# SCH_relayboard.net
KiCad netlist of a schematic drawn in EasyEDA
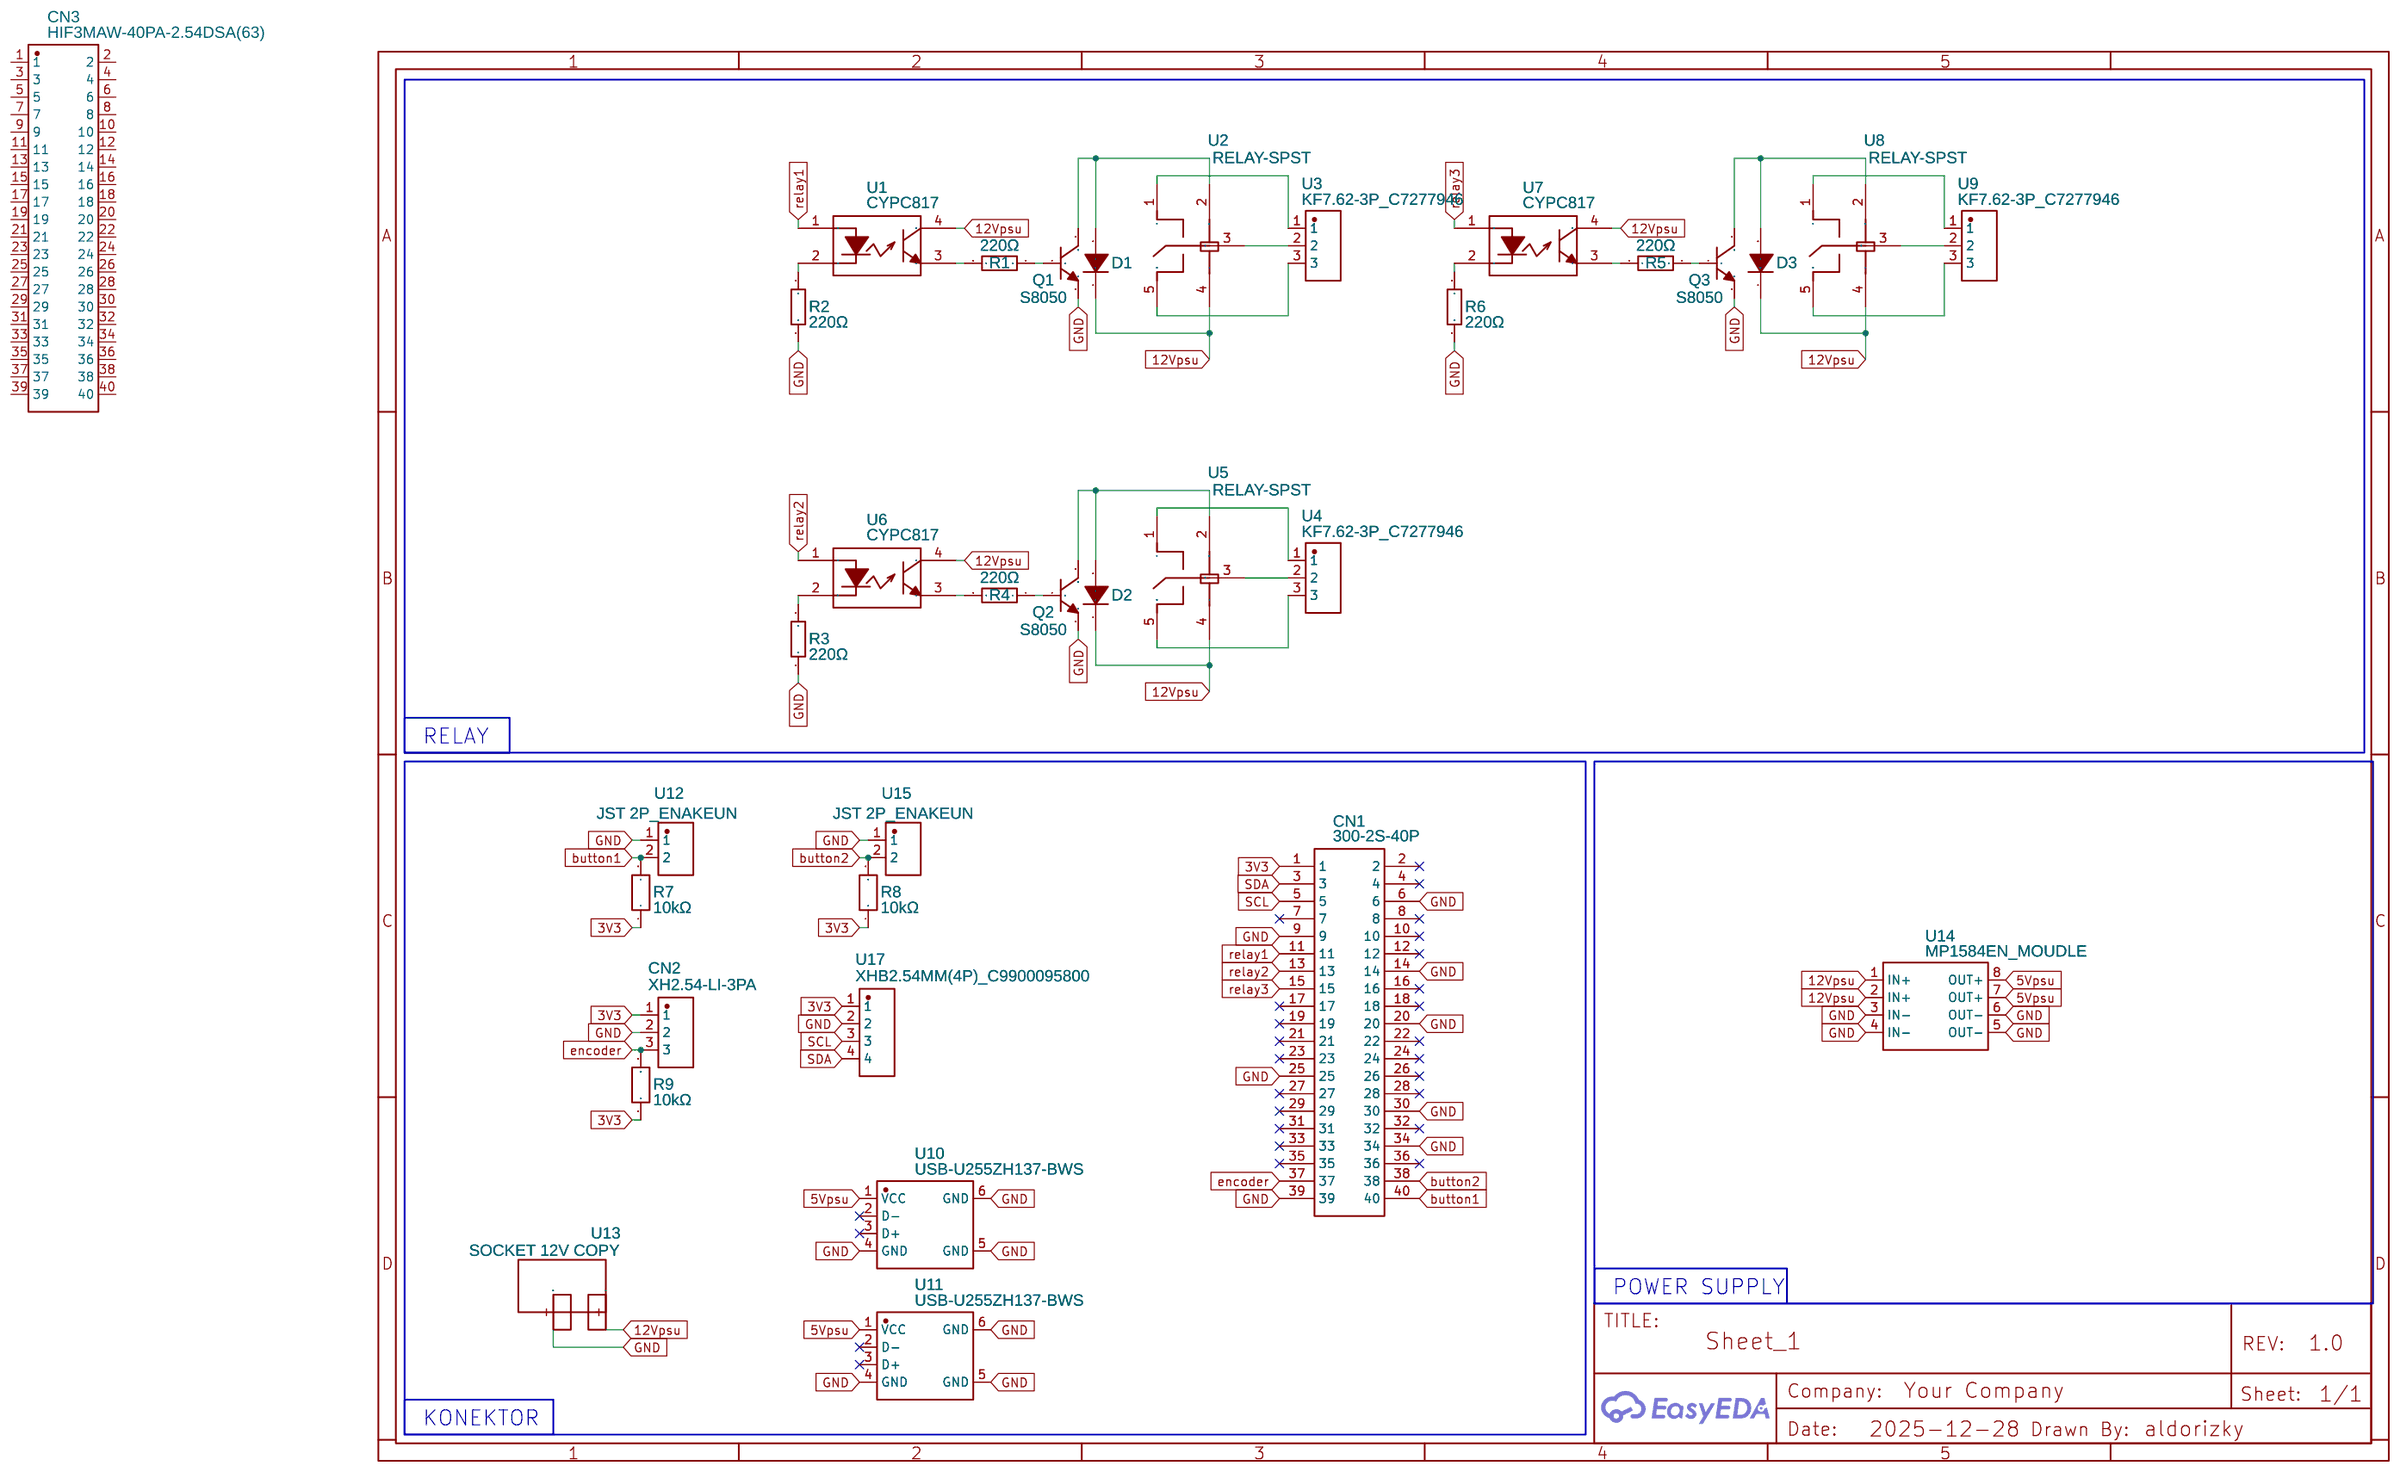
[diagram p0: schematic sheet]

(export (version "E")
  (design (tool "Eeschema 10.0.6"))
  (components
    (comp (ref "CN1")
      (value "300-2S-40P")
      (fields (field (name "Manufacturer Part") "B-3002S40P-0110") (field (name "Manufacturer") "Ckmtw(灿科盟)"))
      (libsource (lib "") (part "300-2S-40P"))
    )
    (comp (ref "CN2") (value "XH2.54-LI-3PA") (libsource (lib "") (part "XH2.54-LI-3PA")))
    (comp (ref "CN3")
      (value "HIF3MAW-40PA-2.54DSA(63)")
      (fields (field (name "Manufacturer") "HRS(广濑)"))
      (libsource (lib "") (part "HIF3MAW-40PA-2.54DSA(63)"))
    )
    (comp (ref "D1")
      (value "1N4148WL")
      (fields (field (name "Manufacturer") "晶导微电子"))
      (libsource (lib "") (part "1N4148WL"))
    )
    (comp (ref "D2")
      (value "1N4148WL")
      (fields (field (name "Manufacturer") "晶导微电子"))
      (libsource (lib "") (part "1N4148WL"))
    )
    (comp (ref "D3")
      (value "1N4148WL")
      (fields (field (name "Manufacturer") "晶导微电子"))
      (libsource (lib "") (part "1N4148WL"))
    )
    (comp (ref "Q1")
      (value "S8050")
      (fields (field (name "Manufacturer") "JUXING(钜兴)"))
      (libsource (lib "") (part "S8050_C3011093"))
    )
    (comp (ref "Q2")
      (value "S8050")
      (fields (field (name "Manufacturer") "JUXING(钜兴)"))
      (libsource (lib "") (part "S8050_C3011093"))
    )
    (comp (ref "Q3")
      (value "S8050")
      (fields (field (name "Manufacturer") "JUXING(钜兴)"))
      (libsource (lib "") (part "S8050_C3011093"))
    )
    (comp (ref "R1")
      (value "220Ω")
      (fields (field (name "Manufacturer Part") "AC0603JR-07220RL") (field (name "Manufacturer") "YAGEO(国巨)"))
      (libsource (lib "") (part "AC0603JR-07220RL_1"))
    )
    (comp (ref "R2")
      (value "220Ω")
      (fields (field (name "Manufacturer Part") "AC0603JR-07220RL") (field (name "Manufacturer") "YAGEO(国巨)"))
      (libsource (lib "") (part "AC0603JR-07220RL"))
    )
    (comp (ref "R3")
      (value "220Ω")
      (fields (field (name "Manufacturer Part") "AC0603JR-07220RL") (field (name "Manufacturer") "YAGEO(国巨)"))
      (libsource (lib "") (part "AC0603JR-07220RL"))
    )
    (comp (ref "R4")
      (value "220Ω")
      (fields (field (name "Manufacturer Part") "AC0603JR-07220RL") (field (name "Manufacturer") "YAGEO(国巨)"))
      (libsource (lib "") (part "AC0603JR-07220RL_1"))
    )
    (comp (ref "R5")
      (value "220Ω")
      (fields (field (name "Manufacturer Part") "AC0603JR-07220RL") (field (name "Manufacturer") "YAGEO(国巨)"))
      (libsource (lib "") (part "AC0603JR-07220RL_1"))
    )
    (comp (ref "R6")
      (value "220Ω")
      (fields (field (name "Manufacturer Part") "AC0603JR-07220RL") (field (name "Manufacturer") "YAGEO(国巨)"))
      (libsource (lib "") (part "AC0603JR-07220RL"))
    )
    (comp (ref "R7")
      (value "10kΩ")
      (fields (field (name "Manufacturer Part") "RC0603FR-1010KL") (field (name "Manufacturer") "YAGEO(国巨)"))
      (libsource (lib "") (part "RC0603FR-1010KL"))
    )
    (comp (ref "R8")
      (value "10kΩ")
      (fields (field (name "Manufacturer Part") "RC0603FR-1010KL") (field (name "Manufacturer") "YAGEO(国巨)"))
      (libsource (lib "") (part "RC0603FR-1010KL"))
    )
    (comp (ref "R9")
      (value "10kΩ")
      (fields (field (name "Manufacturer Part") "RC0603FR-1010KL") (field (name "Manufacturer") "YAGEO(国巨)"))
      (libsource (lib "") (part "RC0603FR-1010KL"))
    )
    (comp (ref "U1")
      (value "CYPC817")
      (fields (field (name "Manufacturer Part") "CYPC817B") (field (name "Manufacturer") "OCIC(卓睿科)"))
      (libsource (lib "") (part "CYPC817"))
    )
    (comp (ref "U2")
      (value "RELAY-SPST")
      (fields (field (name "Manufacturer Part") "Relay-SPST"))
      (libsource (lib "") (part "RELAY-SPST"))
    )
    (comp (ref "U3")
      (value "KF7.62-3P_C7277946")
      (fields (field (name "Manufacturer Part") "KF7.62-3P") (field (name "Manufacturer") "KEFA(科发)"))
      (libsource (lib "") (part "KF7.62-3P_C7277946"))
    )
    (comp (ref "U4")
      (value "KF7.62-3P_C7277946")
      (fields (field (name "Manufacturer Part") "KF7.62-3P") (field (name "Manufacturer") "KEFA(科发)"))
      (libsource (lib "") (part "KF7.62-3P_C7277946"))
    )
    (comp (ref "U5")
      (value "RELAY-SPST")
      (fields (field (name "Manufacturer Part") "Relay-SPST"))
      (libsource (lib "") (part "RELAY-SPST"))
    )
    (comp (ref "U6")
      (value "CYPC817")
      (fields (field (name "Manufacturer Part") "CYPC817B") (field (name "Manufacturer") "OCIC(卓睿科)"))
      (libsource (lib "") (part "CYPC817"))
    )
    (comp (ref "U7")
      (value "CYPC817")
      (fields (field (name "Manufacturer Part") "CYPC817B") (field (name "Manufacturer") "OCIC(卓睿科)"))
      (libsource (lib "") (part "CYPC817"))
    )
    (comp (ref "U8")
      (value "RELAY-SPST")
      (fields (field (name "Manufacturer Part") "Relay-SPST"))
      (libsource (lib "") (part "RELAY-SPST"))
    )
    (comp (ref "U9")
      (value "KF7.62-3P_C7277946")
      (fields (field (name "Manufacturer Part") "KF7.62-3P") (field (name "Manufacturer") "KEFA(科发)"))
      (libsource (lib "") (part "KF7.62-3P_C7277946"))
    )
    (comp (ref "U10")
      (value "USB-U255ZH137-BWS")
      (fields (field (name "Manufacturer") "HANBO(汉博)"))
      (libsource (lib "") (part "USB-U255ZH137-BWS"))
    )
    (comp (ref "U11")
      (value "USB-U255ZH137-BWS")
      (fields (field (name "Manufacturer") "HANBO(汉博)"))
      (libsource (lib "") (part "USB-U255ZH137-BWS"))
    )
    (comp (ref "U12")
      (value "JST 2P_ENAKEUN")
      (fields (field (name "Manufacturer Part") "XH-2P-2.54"))
      (libsource (lib "") (part "JST 2P_ENAKEUN"))
    )
    (comp (ref "U13") (value "SOCKET 12V COPY") (libsource (lib "") (part "SOCKET 12V COPY")))
    (comp (ref "U14")
      (value "MP1584EN_MOUDLE")
      (fields (field (name "Manufacturer Part") "MP1584EN_moudle"))
      (libsource (lib "") (part "MP1584EN_MOUDLE"))
    )
    (comp (ref "U15")
      (value "JST 2P_ENAKEUN")
      (fields (field (name "Manufacturer Part") "XH-2P-2.54"))
      (libsource (lib "") (part "JST 2P_ENAKEUN"))
    )
    (comp (ref "U17")
      (value "XHB2.54MM(4P)_C9900095800")
      (fields (field (name "Manufacturer Part") "XHB2.54mm(4P)"))
      (libsource (lib "") (part "XHB2.54MM(4P)_C9900095800"))
    )
  )
  (nets
    (net (code "1") (name "3V3") (class "Default")
      (node (ref "CN1") (pin "1") (pinfunction "1_1") (pintype "unspecified"))
      (node (ref "CN2") (pin "1") (pinfunction "1_1") (pintype "unspecified"))
      (node (ref "R7") (pin "1") (pinfunction "1_1") (pintype "unspecified"))
      (node (ref "R8") (pin "1") (pinfunction "1_1") (pintype "unspecified"))
      (node (ref "R9") (pin "1") (pinfunction "1_1") (pintype "unspecified"))
      (node (ref "U17") (pin "1") (pinfunction "1_1") (pintype "unspecified"))
    )
    (net (code "2") (name "5Vpsu") (class "Default")
      (node (ref "U10") (pin "1") (pinfunction "VCC_1") (pintype "unspecified"))
      (node (ref "U11") (pin "1") (pinfunction "VCC_1") (pintype "unspecified"))
      (node (ref "U14") (pin "7") (pinfunction "OUT+_7") (pintype "unspecified"))
      (node (ref "U14") (pin "8") (pinfunction "OUT+_8") (pintype "unspecified"))
    )
    (net (code "3") (name "12Vpsu") (class "Default")
      (node (ref "D1") (pin "1") (pinfunction "C_1") (pintype "unspecified"))
      (node (ref "D2") (pin "1") (pinfunction "C_1") (pintype "unspecified"))
      (node (ref "D3") (pin "1") (pinfunction "C_1") (pintype "unspecified"))
      (node (ref "U1") (pin "4") (pinfunction "COL_4") (pintype "unspecified"))
      (node (ref "U13") (pin "+") (pinfunction "1_+") (pintype "unspecified"))
      (node (ref "U14") (pin "1") (pinfunction "IN+_1") (pintype "unspecified"))
      (node (ref "U14") (pin "2") (pinfunction "IN+_2") (pintype "unspecified"))
      (node (ref "U2") (pin "4") (pinfunction "4_4") (pintype "unspecified"))
      (node (ref "U5") (pin "4") (pinfunction "4_4") (pintype "unspecified"))
      (node (ref "U6") (pin "4") (pinfunction "COL_4") (pintype "unspecified"))
      (node (ref "U7") (pin "4") (pinfunction "COL_4") (pintype "unspecified"))
      (node (ref "U8") (pin "4") (pinfunction "4_4") (pintype "unspecified"))
    )
    (net (code "4") (name "GND") (class "Default")
      (node (ref "CN1") (pin "14") (pinfunction "14_14") (pintype "unspecified"))
      (node (ref "CN1") (pin "20") (pinfunction "20_20") (pintype "unspecified"))
      (node (ref "CN1") (pin "25") (pinfunction "25_25") (pintype "unspecified"))
      (node (ref "CN1") (pin "30") (pinfunction "30_30") (pintype "unspecified"))
      (node (ref "CN1") (pin "34") (pinfunction "34_34") (pintype "unspecified"))
      (node (ref "CN1") (pin "39") (pinfunction "39_39") (pintype "unspecified"))
      (node (ref "CN1") (pin "6") (pinfunction "6_6") (pintype "unspecified"))
      (node (ref "CN1") (pin "9") (pinfunction "9_9") (pintype "unspecified"))
      (node (ref "CN2") (pin "2") (pinfunction "2_2") (pintype "unspecified"))
      (node (ref "Q1") (pin "2") (pinfunction "E_2") (pintype "unspecified"))
      (node (ref "Q2") (pin "2") (pinfunction "E_2") (pintype "unspecified"))
      (node (ref "Q3") (pin "2") (pinfunction "E_2") (pintype "unspecified"))
      (node (ref "R2") (pin "1") (pinfunction "1_1") (pintype "unspecified"))
      (node (ref "R3") (pin "1") (pinfunction "1_1") (pintype "unspecified"))
      (node (ref "R6") (pin "1") (pinfunction "1_1") (pintype "unspecified"))
      (node (ref "U10") (pin "4") (pinfunction "GND_4") (pintype "unspecified"))
      (node (ref "U10") (pin "5") (pinfunction "GND_5") (pintype "unspecified"))
      (node (ref "U10") (pin "6") (pinfunction "GND_6") (pintype "unspecified"))
      (node (ref "U11") (pin "4") (pinfunction "GND_4") (pintype "unspecified"))
      (node (ref "U11") (pin "5") (pinfunction "GND_5") (pintype "unspecified"))
      (node (ref "U11") (pin "6") (pinfunction "GND_6") (pintype "unspecified"))
      (node (ref "U12") (pin "1") (pinfunction "1_1") (pintype "unspecified"))
      (node (ref "U13") (pin "-") (pinfunction "2_-") (pintype "unspecified"))
      (node (ref "U14") (pin "3") (pinfunction "IN-_3") (pintype "unspecified"))
      (node (ref "U14") (pin "4") (pinfunction "IN-_4") (pintype "unspecified"))
      (node (ref "U14") (pin "5") (pinfunction "OUT-_5") (pintype "unspecified"))
      (node (ref "U14") (pin "6") (pinfunction "OUT-_6") (pintype "unspecified"))
      (node (ref "U15") (pin "1") (pinfunction "1_1") (pintype "unspecified"))
      (node (ref "U17") (pin "2") (pinfunction "2_2") (pintype "unspecified"))
    )
    (net (code "5") (name "Net-(D1-A)") (class "Default")
      (node (ref "D1") (pin "2") (pinfunction "A_2") (pintype "unspecified"))
      (node (ref "Q1") (pin "3") (pinfunction "C_3") (pintype "unspecified"))
      (node (ref "U2") (pin "2") (pinfunction "2_2") (pintype "unspecified"))
    )
    (net (code "6") (name "Net-(D2-A)") (class "Default")
      (node (ref "D2") (pin "2") (pinfunction "A_2") (pintype "unspecified"))
      (node (ref "Q2") (pin "3") (pinfunction "C_3") (pintype "unspecified"))
      (node (ref "U5") (pin "2") (pinfunction "2_2") (pintype "unspecified"))
    )
    (net (code "7") (name "Net-(D3-A)") (class "Default")
      (node (ref "D3") (pin "2") (pinfunction "A_2") (pintype "unspecified"))
      (node (ref "Q3") (pin "3") (pinfunction "C_3") (pintype "unspecified"))
      (node (ref "U8") (pin "2") (pinfunction "2_2") (pintype "unspecified"))
    )
    (net (code "8") (name "Net-(Q1-B)") (class "Default")
      (node (ref "Q1") (pin "1") (pinfunction "B_1") (pintype "unspecified"))
      (node (ref "R1") (pin "1") (pinfunction "1_1") (pintype "unspecified"))
    )
    (net (code "9") (name "Net-(Q2-B)") (class "Default")
      (node (ref "Q2") (pin "1") (pinfunction "B_1") (pintype "unspecified"))
      (node (ref "R4") (pin "1") (pinfunction "1_1") (pintype "unspecified"))
    )
    (net (code "10") (name "Net-(Q3-B)") (class "Default")
      (node (ref "Q3") (pin "1") (pinfunction "B_1") (pintype "unspecified"))
      (node (ref "R5") (pin "1") (pinfunction "1_1") (pintype "unspecified"))
    )
    (net (code "11") (name "Net-(U1-CAT)") (class "Default")
      (node (ref "R2") (pin "2") (pinfunction "2_2") (pintype "unspecified"))
      (node (ref "U1") (pin "2") (pinfunction "CAT_2") (pintype "unspecified"))
    )
    (net (code "12") (name "Net-(U1-EM)") (class "Default")
      (node (ref "R1") (pin "2") (pinfunction "2_2") (pintype "unspecified"))
      (node (ref "U1") (pin "3") (pinfunction "EM_3") (pintype "unspecified"))
    )
    (net (code "13") (name "Net-(U2-Pad1)") (class "Default")
      (node (ref "U2") (pin "1") (pinfunction "1_1") (pintype "unspecified"))
      (node (ref "U3") (pin "1") (pinfunction "1_1") (pintype "unspecified"))
    )
    (net (code "14") (name "Net-(U2-Pad3)") (class "Default")
      (node (ref "U2") (pin "3") (pinfunction "3_3") (pintype "unspecified"))
      (node (ref "U3") (pin "2") (pinfunction "2_2") (pintype "unspecified"))
    )
    (net (code "15") (name "Net-(U2-Pad5)") (class "Default")
      (node (ref "U2") (pin "5") (pinfunction "5_5") (pintype "unspecified"))
      (node (ref "U3") (pin "3") (pinfunction "3_3") (pintype "unspecified"))
    )
    (net (code "16") (name "Net-(U4-Pad1)") (class "Default")
      (node (ref "U4") (pin "1") (pinfunction "1_1") (pintype "unspecified"))
      (node (ref "U5") (pin "1") (pinfunction "1_1") (pintype "unspecified"))
    )
    (net (code "17") (name "Net-(U4-Pad2)") (class "Default")
      (node (ref "U4") (pin "2") (pinfunction "2_2") (pintype "unspecified"))
      (node (ref "U5") (pin "3") (pinfunction "3_3") (pintype "unspecified"))
    )
    (net (code "18") (name "Net-(U4-Pad3)") (class "Default")
      (node (ref "U4") (pin "3") (pinfunction "3_3") (pintype "unspecified"))
      (node (ref "U5") (pin "5") (pinfunction "5_5") (pintype "unspecified"))
    )
    (net (code "19") (name "Net-(U6-CAT)") (class "Default")
      (node (ref "R3") (pin "2") (pinfunction "2_2") (pintype "unspecified"))
      (node (ref "U6") (pin "2") (pinfunction "CAT_2") (pintype "unspecified"))
    )
    (net (code "20") (name "Net-(U6-EM)") (class "Default")
      (node (ref "R4") (pin "2") (pinfunction "2_2") (pintype "unspecified"))
      (node (ref "U6") (pin "3") (pinfunction "EM_3") (pintype "unspecified"))
    )
    (net (code "21") (name "Net-(U7-CAT)") (class "Default")
      (node (ref "R6") (pin "2") (pinfunction "2_2") (pintype "unspecified"))
      (node (ref "U7") (pin "2") (pinfunction "CAT_2") (pintype "unspecified"))
    )
    (net (code "22") (name "Net-(U7-EM)") (class "Default")
      (node (ref "R5") (pin "2") (pinfunction "2_2") (pintype "unspecified"))
      (node (ref "U7") (pin "3") (pinfunction "EM_3") (pintype "unspecified"))
    )
    (net (code "23") (name "Net-(U8-Pad1)") (class "Default")
      (node (ref "U8") (pin "1") (pinfunction "1_1") (pintype "unspecified"))
      (node (ref "U9") (pin "1") (pinfunction "1_1") (pintype "unspecified"))
    )
    (net (code "24") (name "Net-(U8-Pad3)") (class "Default")
      (node (ref "U8") (pin "3") (pinfunction "3_3") (pintype "unspecified"))
      (node (ref "U9") (pin "2") (pinfunction "2_2") (pintype "unspecified"))
    )
    (net (code "25") (name "Net-(U8-Pad5)") (class "Default")
      (node (ref "U8") (pin "5") (pinfunction "5_5") (pintype "unspecified"))
      (node (ref "U9") (pin "3") (pinfunction "3_3") (pintype "unspecified"))
    )
    (net (code "26") (name "SCL") (class "Default")
      (node (ref "CN1") (pin "5") (pinfunction "5_5") (pintype "unspecified"))
      (node (ref "U17") (pin "3") (pinfunction "3_3") (pintype "unspecified"))
    )
    (net (code "27") (name "SDA") (class "Default")
      (node (ref "CN1") (pin "3") (pinfunction "3_3") (pintype "unspecified"))
      (node (ref "U17") (pin "4") (pinfunction "4_4") (pintype "unspecified"))
    )
    (net (code "28") (name "button1") (class "Default")
      (node (ref "CN1") (pin "40") (pinfunction "40_40") (pintype "unspecified"))
      (node (ref "R7") (pin "2") (pinfunction "2_2") (pintype "unspecified"))
      (node (ref "U12") (pin "2") (pinfunction "2_2") (pintype "unspecified"))
    )
    (net (code "29") (name "button2") (class "Default")
      (node (ref "CN1") (pin "38") (pinfunction "38_38") (pintype "unspecified"))
      (node (ref "R8") (pin "2") (pinfunction "2_2") (pintype "unspecified"))
      (node (ref "U15") (pin "2") (pinfunction "2_2") (pintype "unspecified"))
    )
    (net (code "30") (name "encoder") (class "Default")
      (node (ref "CN1") (pin "37") (pinfunction "37_37") (pintype "unspecified"))
      (node (ref "CN2") (pin "3") (pinfunction "3_3") (pintype "unspecified"))
      (node (ref "R9") (pin "2") (pinfunction "2_2") (pintype "unspecified"))
    )
    (net (code "31") (name "relay1") (class "Default")
      (node (ref "CN1") (pin "11") (pinfunction "11_11") (pintype "unspecified"))
      (node (ref "U1") (pin "1") (pinfunction "AN_1") (pintype "unspecified"))
    )
    (net (code "32") (name "relay2") (class "Default")
      (node (ref "CN1") (pin "13") (pinfunction "13_13") (pintype "unspecified"))
      (node (ref "U6") (pin "1") (pinfunction "AN_1") (pintype "unspecified"))
    )
    (net (code "33") (name "relay3") (class "Default")
      (node (ref "CN1") (pin "15") (pinfunction "15_15") (pintype "unspecified"))
      (node (ref "U7") (pin "1") (pinfunction "AN_1") (pintype "unspecified"))
    )
    (net (code "34") (name "unconnected-(CN1-Pad2)") (class "Default")
      (node (ref "CN1") (pin "2") (pinfunction "2_2") (pintype "unspecified+no_connect"))
    )
    (net (code "35") (name "unconnected-(CN1-Pad4)") (class "Default")
      (node (ref "CN1") (pin "4") (pinfunction "4_4") (pintype "unspecified+no_connect"))
    )
    (net (code "36") (name "unconnected-(CN1-Pad7)") (class "Default")
      (node (ref "CN1") (pin "7") (pinfunction "7_7") (pintype "unspecified+no_connect"))
    )
    (net (code "37") (name "unconnected-(CN1-Pad8)") (class "Default")
      (node (ref "CN1") (pin "8") (pinfunction "8_8") (pintype "unspecified+no_connect"))
    )
    (net (code "38") (name "unconnected-(CN1-Pad10)") (class "Default")
      (node (ref "CN1") (pin "10") (pinfunction "10_10") (pintype "unspecified+no_connect"))
    )
    (net (code "39") (name "unconnected-(CN1-Pad12)") (class "Default")
      (node (ref "CN1") (pin "12") (pinfunction "12_12") (pintype "unspecified+no_connect"))
    )
    (net (code "40") (name "unconnected-(CN1-Pad16)") (class "Default")
      (node (ref "CN1") (pin "16") (pinfunction "16_16") (pintype "unspecified+no_connect"))
    )
    (net (code "41") (name "unconnected-(CN1-Pad17)") (class "Default")
      (node (ref "CN1") (pin "17") (pinfunction "17_17") (pintype "unspecified+no_connect"))
    )
    (net (code "42") (name "unconnected-(CN1-Pad18)") (class "Default")
      (node (ref "CN1") (pin "18") (pinfunction "18_18") (pintype "unspecified+no_connect"))
    )
    (net (code "43") (name "unconnected-(CN1-Pad19)") (class "Default")
      (node (ref "CN1") (pin "19") (pinfunction "19_19") (pintype "unspecified+no_connect"))
    )
    (net (code "44") (name "unconnected-(CN1-Pad21)") (class "Default")
      (node (ref "CN1") (pin "21") (pinfunction "21_21") (pintype "unspecified+no_connect"))
    )
    (net (code "45") (name "unconnected-(CN1-Pad22)") (class "Default")
      (node (ref "CN1") (pin "22") (pinfunction "22_22") (pintype "unspecified+no_connect"))
    )
    (net (code "46") (name "unconnected-(CN1-Pad23)") (class "Default")
      (node (ref "CN1") (pin "23") (pinfunction "23_23") (pintype "unspecified+no_connect"))
    )
    (net (code "47") (name "unconnected-(CN1-Pad24)") (class "Default")
      (node (ref "CN1") (pin "24") (pinfunction "24_24") (pintype "unspecified+no_connect"))
    )
    (net (code "48") (name "unconnected-(CN1-Pad26)") (class "Default")
      (node (ref "CN1") (pin "26") (pinfunction "26_26") (pintype "unspecified+no_connect"))
    )
    (net (code "49") (name "unconnected-(CN1-Pad27)") (class "Default")
      (node (ref "CN1") (pin "27") (pinfunction "27_27") (pintype "unspecified+no_connect"))
    )
    (net (code "50") (name "unconnected-(CN1-Pad28)") (class "Default")
      (node (ref "CN1") (pin "28") (pinfunction "28_28") (pintype "unspecified+no_connect"))
    )
    (net (code "51") (name "unconnected-(CN1-Pad29)") (class "Default")
      (node (ref "CN1") (pin "29") (pinfunction "29_29") (pintype "unspecified+no_connect"))
    )
    (net (code "52") (name "unconnected-(CN1-Pad31)") (class "Default")
      (node (ref "CN1") (pin "31") (pinfunction "31_31") (pintype "unspecified+no_connect"))
    )
    (net (code "53") (name "unconnected-(CN1-Pad32)") (class "Default")
      (node (ref "CN1") (pin "32") (pinfunction "32_32") (pintype "unspecified+no_connect"))
    )
    (net (code "54") (name "unconnected-(CN1-Pad33)") (class "Default")
      (node (ref "CN1") (pin "33") (pinfunction "33_33") (pintype "unspecified+no_connect"))
    )
    (net (code "55") (name "unconnected-(CN1-Pad35)") (class "Default")
      (node (ref "CN1") (pin "35") (pinfunction "35_35") (pintype "unspecified+no_connect"))
    )
    (net (code "56") (name "unconnected-(CN1-Pad36)") (class "Default")
      (node (ref "CN1") (pin "36") (pinfunction "36_36") (pintype "unspecified+no_connect"))
    )
    (net (code "57") (name "unconnected-(CN3-Pad1)") (class "Default")
      (node (ref "CN3") (pin "1") (pinfunction "1_1") (pintype "unspecified"))
    )
    (net (code "58") (name "unconnected-(CN3-Pad2)") (class "Default")
      (node (ref "CN3") (pin "2") (pinfunction "2_2") (pintype "unspecified"))
    )
    (net (code "59") (name "unconnected-(CN3-Pad3)") (class "Default")
      (node (ref "CN3") (pin "3") (pinfunction "3_3") (pintype "unspecified"))
    )
    (net (code "60") (name "unconnected-(CN3-Pad4)") (class "Default")
      (node (ref "CN3") (pin "4") (pinfunction "4_4") (pintype "unspecified"))
    )
    (net (code "61") (name "unconnected-(CN3-Pad5)") (class "Default")
      (node (ref "CN3") (pin "5") (pinfunction "5_5") (pintype "unspecified"))
    )
    (net (code "62") (name "unconnected-(CN3-Pad6)") (class "Default")
      (node (ref "CN3") (pin "6") (pinfunction "6_6") (pintype "unspecified"))
    )
    (net (code "63") (name "unconnected-(CN3-Pad7)") (class "Default")
      (node (ref "CN3") (pin "7") (pinfunction "7_7") (pintype "unspecified"))
    )
    (net (code "64") (name "unconnected-(CN3-Pad8)") (class "Default")
      (node (ref "CN3") (pin "8") (pinfunction "8_8") (pintype "unspecified"))
    )
    (net (code "65") (name "unconnected-(CN3-Pad9)") (class "Default")
      (node (ref "CN3") (pin "9") (pinfunction "9_9") (pintype "unspecified"))
    )
    (net (code "66") (name "unconnected-(CN3-Pad10)") (class "Default")
      (node (ref "CN3") (pin "10") (pinfunction "10_10") (pintype "unspecified"))
    )
    (net (code "67") (name "unconnected-(CN3-Pad11)") (class "Default")
      (node (ref "CN3") (pin "11") (pinfunction "11_11") (pintype "unspecified"))
    )
    (net (code "68") (name "unconnected-(CN3-Pad12)") (class "Default")
      (node (ref "CN3") (pin "12") (pinfunction "12_12") (pintype "unspecified"))
    )
    (net (code "69") (name "unconnected-(CN3-Pad13)") (class "Default")
      (node (ref "CN3") (pin "13") (pinfunction "13_13") (pintype "unspecified"))
    )
    (net (code "70") (name "unconnected-(CN3-Pad14)") (class "Default")
      (node (ref "CN3") (pin "14") (pinfunction "14_14") (pintype "unspecified"))
    )
    (net (code "71") (name "unconnected-(CN3-Pad15)") (class "Default")
      (node (ref "CN3") (pin "15") (pinfunction "15_15") (pintype "unspecified"))
    )
    (net (code "72") (name "unconnected-(CN3-Pad16)") (class "Default")
      (node (ref "CN3") (pin "16") (pinfunction "16_16") (pintype "unspecified"))
    )
    (net (code "73") (name "unconnected-(CN3-Pad17)") (class "Default")
      (node (ref "CN3") (pin "17") (pinfunction "17_17") (pintype "unspecified"))
    )
    (net (code "74") (name "unconnected-(CN3-Pad18)") (class "Default")
      (node (ref "CN3") (pin "18") (pinfunction "18_18") (pintype "unspecified"))
    )
    (net (code "75") (name "unconnected-(CN3-Pad19)") (class "Default")
      (node (ref "CN3") (pin "19") (pinfunction "19_19") (pintype "unspecified"))
    )
    (net (code "76") (name "unconnected-(CN3-Pad20)") (class "Default")
      (node (ref "CN3") (pin "20") (pinfunction "20_20") (pintype "unspecified"))
    )
    (net (code "77") (name "unconnected-(CN3-Pad21)") (class "Default")
      (node (ref "CN3") (pin "21") (pinfunction "21_21") (pintype "unspecified"))
    )
    (net (code "78") (name "unconnected-(CN3-Pad22)") (class "Default")
      (node (ref "CN3") (pin "22") (pinfunction "22_22") (pintype "unspecified"))
    )
    (net (code "79") (name "unconnected-(CN3-Pad23)") (class "Default")
      (node (ref "CN3") (pin "23") (pinfunction "23_23") (pintype "unspecified"))
    )
    (net (code "80") (name "unconnected-(CN3-Pad24)") (class "Default")
      (node (ref "CN3") (pin "24") (pinfunction "24_24") (pintype "unspecified"))
    )
    (net (code "81") (name "unconnected-(CN3-Pad25)") (class "Default")
      (node (ref "CN3") (pin "25") (pinfunction "25_25") (pintype "unspecified"))
    )
    (net (code "82") (name "unconnected-(CN3-Pad26)") (class "Default")
      (node (ref "CN3") (pin "26") (pinfunction "26_26") (pintype "unspecified"))
    )
    (net (code "83") (name "unconnected-(CN3-Pad27)") (class "Default")
      (node (ref "CN3") (pin "27") (pinfunction "27_27") (pintype "unspecified"))
    )
    (net (code "84") (name "unconnected-(CN3-Pad28)") (class "Default")
      (node (ref "CN3") (pin "28") (pinfunction "28_28") (pintype "unspecified"))
    )
    (net (code "85") (name "unconnected-(CN3-Pad29)") (class "Default")
      (node (ref "CN3") (pin "29") (pinfunction "29_29") (pintype "unspecified"))
    )
    (net (code "86") (name "unconnected-(CN3-Pad30)") (class "Default")
      (node (ref "CN3") (pin "30") (pinfunction "30_30") (pintype "unspecified"))
    )
    (net (code "87") (name "unconnected-(CN3-Pad31)") (class "Default")
      (node (ref "CN3") (pin "31") (pinfunction "31_31") (pintype "unspecified"))
    )
    (net (code "88") (name "unconnected-(CN3-Pad32)") (class "Default")
      (node (ref "CN3") (pin "32") (pinfunction "32_32") (pintype "unspecified"))
    )
    (net (code "89") (name "unconnected-(CN3-Pad33)") (class "Default")
      (node (ref "CN3") (pin "33") (pinfunction "33_33") (pintype "unspecified"))
    )
    (net (code "90") (name "unconnected-(CN3-Pad34)") (class "Default")
      (node (ref "CN3") (pin "34") (pinfunction "34_34") (pintype "unspecified"))
    )
    (net (code "91") (name "unconnected-(CN3-Pad35)") (class "Default")
      (node (ref "CN3") (pin "35") (pinfunction "35_35") (pintype "unspecified"))
    )
    (net (code "92") (name "unconnected-(CN3-Pad36)") (class "Default")
      (node (ref "CN3") (pin "36") (pinfunction "36_36") (pintype "unspecified"))
    )
    (net (code "93") (name "unconnected-(CN3-Pad37)") (class "Default")
      (node (ref "CN3") (pin "37") (pinfunction "37_37") (pintype "unspecified"))
    )
    (net (code "94") (name "unconnected-(CN3-Pad38)") (class "Default")
      (node (ref "CN3") (pin "38") (pinfunction "38_38") (pintype "unspecified"))
    )
    (net (code "95") (name "unconnected-(CN3-Pad39)") (class "Default")
      (node (ref "CN3") (pin "39") (pinfunction "39_39") (pintype "unspecified"))
    )
    (net (code "96") (name "unconnected-(CN3-Pad40)") (class "Default")
      (node (ref "CN3") (pin "40") (pinfunction "40_40") (pintype "unspecified"))
    )
    (net (code "97") (name "unconnected-(U10-D+-Pad3)") (class "Default")
      (node (ref "U10") (pin "3") (pinfunction "D+_3") (pintype "unspecified+no_connect"))
    )
    (net (code "98") (name "unconnected-(U10-D--Pad2)") (class "Default")
      (node (ref "U10") (pin "2") (pinfunction "D-_2") (pintype "unspecified+no_connect"))
    )
    (net (code "99") (name "unconnected-(U11-D+-Pad3)") (class "Default")
      (node (ref "U11") (pin "3") (pinfunction "D+_3") (pintype "unspecified+no_connect"))
    )
    (net (code "100") (name "unconnected-(U11-D--Pad2)") (class "Default")
      (node (ref "U11") (pin "2") (pinfunction "D-_2") (pintype "unspecified+no_connect"))
    )
  )
)
